# SpeedACQ.net
KiCad netlist of a schematic drawn in Altium Designer
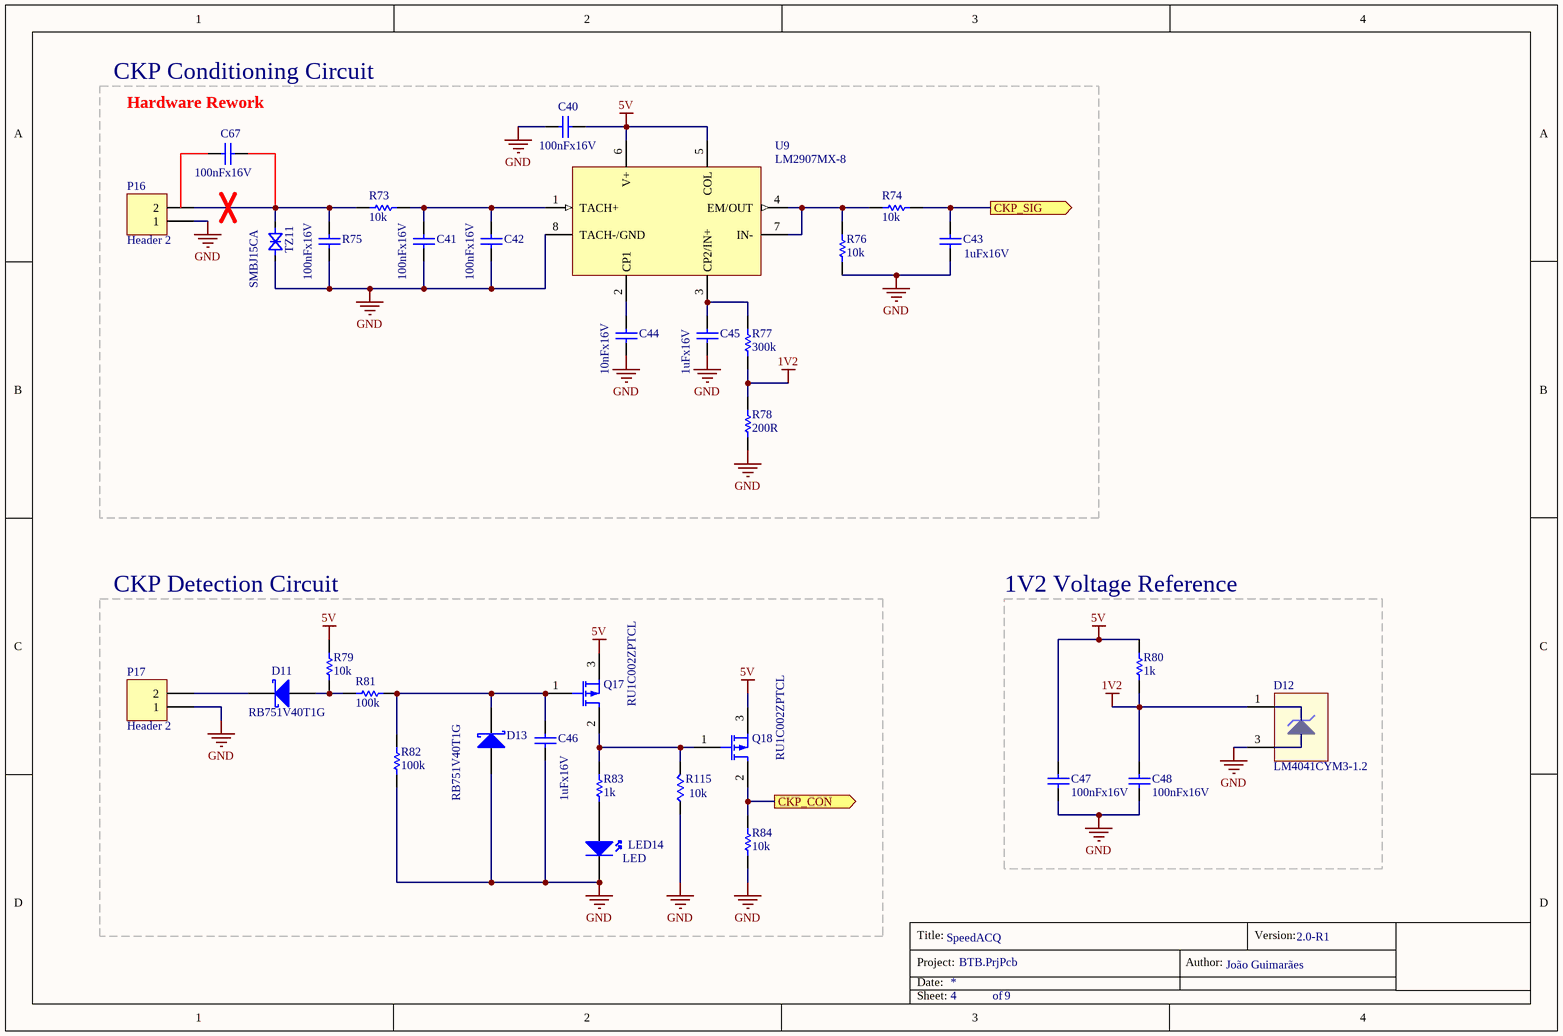
[diagram p0: SpeedACQ.SchDoc]

(export (version "E")
  (design (tool "Eeschema 10.0.6"))
  (components
    (comp (ref "C40")
      (value "100nFx16V")
      (footprint "DISC-0805")
      (description "Capacitor")
      (libsource (lib "IntLib") (part "Cap"))
    )
    (comp (ref "C41")
      (value "100nFx16V")
      (footprint "DISC-0805")
      (description "Capacitor")
      (libsource (lib "IntLib") (part "Cap"))
    )
    (comp (ref "C42")
      (value "100nFx16V")
      (footprint "DISC-0805")
      (description "Capacitor")
      (libsource (lib "IntLib") (part "Cap"))
    )
    (comp (ref "C43")
      (value "1uFx16V")
      (footprint "DISC-0805")
      (description "Capacitor")
      (libsource (lib "IntLib") (part "Cap"))
    )
    (comp (ref "C44")
      (value "10nFx16V")
      (footprint "DISC-0805")
      (description "Capacitor")
      (libsource (lib "IntLib") (part "Cap"))
    )
    (comp (ref "C45")
      (value "1uFx16V")
      (footprint "DISC-0805")
      (description "Capacitor")
      (libsource (lib "IntLib") (part "Cap"))
    )
    (comp (ref "C46")
      (value "1uFx16V")
      (footprint "DISC-0805")
      (description "Capacitor")
      (libsource (lib "IntLib") (part "Cap"))
    )
    (comp (ref "C47")
      (value "100nFx16V")
      (footprint "DISC-0805")
      (description "Capacitor")
      (libsource (lib "IntLib") (part "Cap"))
    )
    (comp (ref "C48")
      (value "100nFx16V")
      (footprint "DISC-0805")
      (description "Capacitor")
      (libsource (lib "IntLib") (part "Cap"))
    )
    (comp (ref "C67")
      (value "100nFx16V")
      (footprint "DISC-0805")
      (description "Capacitor")
      (libsource (lib "IntLib") (part "Cap"))
    )
    (comp (ref "D11")
      (value "RB751V40T1G")
      (footprint "DISC-SOD-323")
      (description "Schottky Diode")
      (fields (field (name "PUBLISHER") "Altium Limited"))
      (libsource (lib "IntLib") (part "D Schottky"))
    )
    (comp (ref "D12")
      (value "LM4041CYM3-1.2")
      (footprint "DISC-SOT-23")
      (description "Shunt Voltage References")
      (libsource (lib "IntLib") (part "LM4040"))
    )
    (comp (ref "D13")
      (value "RB751V40T1G")
      (footprint "DISC-SOD-323")
      (description "Schottky Diode")
      (fields (field (name "PUBLISHER") "Altium Limited"))
      (libsource (lib "IntLib") (part "D Schottky"))
    )
    (comp (ref "LED14") (value "LED") (footprint "DISC-LED-0.1-PTH") (libsource (lib "IntLib") (part "LED")))
    (comp (ref "P16")
      (value "Header 2")
      (footprint "CON-FLEXWIRE-0.5MM2-1X2")
      (description "Header, 2-Pin")
      (fields (field (name "PUBLISHER") "Altium Limited"))
      (libsource (lib "IntLib") (part "Header 2"))
    )
    (comp (ref "P17")
      (value "Header 2")
      (footprint "CON-FLEXWIRE-0.5MM2-1X2")
      (description "Header, 2-Pin")
      (fields (field (name "PUBLISHER") "Altium Limited"))
      (libsource (lib "IntLib") (part "Header 2"))
    )
    (comp (ref "Q17")
      (value "RU1C002ZPTCL")
      (footprint "DISC-SOT-23")
      (description "P-Channel MOSFET")
      (libsource (lib "IntLib") (part "Transistor-PMOS"))
    )
    (comp (ref "Q18")
      (value "RU1C002ZPTCL")
      (footprint "DISC-SOT-23")
      (description "P-Channel MOSFET")
      (libsource (lib "IntLib") (part "Transistor-PMOS"))
    )
    (comp (ref "R73")
      (value "10k")
      (footprint "DISC-0805")
      (description "Resistor")
      (libsource (lib "IntLib") (part "Res"))
    )
    (comp (ref "R74")
      (value "10k")
      (footprint "DISC-0805")
      (description "Resistor")
      (libsource (lib "IntLib") (part "Res"))
    )
    (comp (ref "R75")
      (value "100nFx16V")
      (footprint "DISC-0805")
      (description "Capacitor")
      (libsource (lib "IntLib") (part "Cap"))
    )
    (comp (ref "R76")
      (value "10k")
      (footprint "DISC-0805")
      (description "Resistor")
      (libsource (lib "IntLib") (part "Res"))
    )
    (comp (ref "R77")
      (value "300k")
      (footprint "DISC-0805")
      (description "Resistor")
      (libsource (lib "IntLib") (part "Res"))
    )
    (comp (ref "R78")
      (value "200R")
      (footprint "DISC-0805")
      (description "Resistor")
      (libsource (lib "IntLib") (part "Res"))
    )
    (comp (ref "R79")
      (value "10k")
      (footprint "DISC-0805")
      (description "Resistor")
      (libsource (lib "IntLib") (part "Res"))
    )
    (comp (ref "R80")
      (value "1k")
      (footprint "DISC-0805")
      (description "Resistor")
      (libsource (lib "IntLib") (part "Res"))
    )
    (comp (ref "R81")
      (value "100k")
      (footprint "DISC-0805")
      (description "Resistor")
      (libsource (lib "IntLib") (part "Res"))
    )
    (comp (ref "R82")
      (value "100k")
      (footprint "DISC-0805")
      (description "Resistor")
      (libsource (lib "IntLib") (part "Res"))
    )
    (comp (ref "R83")
      (value "1k")
      (footprint "DISC-0805")
      (description "Resistor")
      (libsource (lib "IntLib") (part "Res"))
    )
    (comp (ref "R84")
      (value "10k")
      (footprint "DISC-0805")
      (description "Resistor")
      (libsource (lib "IntLib") (part "Res"))
    )
    (comp (ref "R115")
      (value "10k")
      (footprint "DISC-0805")
      (description "Resistor")
      (libsource (lib "AUTOTRAC") (part "RESISTOR"))
    )
    (comp (ref "TZ11")
      (value "SMBJ15CA")
      (footprint "DISC-DO214-AA")
      (description "TVZ-Bi-Directional")
      (libsource (lib "IntLib") (part "TVZ-Bi-Directional"))
    )
    (comp (ref "U9")
      (value "LM2907MX-8")
      (footprint "CI-SOIC-8")
      (description "Voltage to Frequency & Frequency to Voltage Frequency to Voltage Converter")
      (libsource (lib "IntLib") (part "LM2907MX-8"))
    )
  )
  (nets
    (net (code "1") (name "/CKP_CON") (class "Default")
      (node (ref "Q18") (pin "2") (pinfunction "D_2") (pintype "passive"))
      (node (ref "R84") (pin "1") (pinfunction "1_1") (pintype "passive"))
    )
    (net (code "2") (name "/CKP_SIG") (class "Default")
      (node (ref "C43") (pin "2") (pinfunction "2_2") (pintype "passive"))
      (node (ref "R74") (pin "2") (pinfunction "2_2") (pintype "passive"))
    )
    (net (code "3") (name "1V2") (class "Default")
      (node (ref "C48") (pin "1") (pinfunction "1_1") (pintype "passive"))
      (node (ref "D12") (pin "1") (pinfunction "A_1") (pintype "passive"))
      (node (ref "R77") (pin "2") (pinfunction "2_2") (pintype "passive"))
      (node (ref "R78") (pin "1") (pinfunction "1_1") (pintype "passive"))
      (node (ref "R80") (pin "2") (pinfunction "2_2") (pintype "passive"))
    )
    (net (code "4") (name "5V") (class "Default")
      (node (ref "C40") (pin "1") (pinfunction "1_1") (pintype "passive"))
      (node (ref "C47") (pin "1") (pinfunction "1_1") (pintype "passive"))
      (node (ref "Q17") (pin "3") (pinfunction "S_3") (pintype "passive"))
      (node (ref "Q18") (pin "3") (pinfunction "S_3") (pintype "passive"))
      (node (ref "R79") (pin "1") (pinfunction "1_1") (pintype "passive"))
      (node (ref "R80") (pin "1") (pinfunction "1_1") (pintype "passive"))
      (node (ref "U9") (pin "5") (pinfunction "COL_5") (pintype "passive"))
      (node (ref "U9") (pin "6") (pinfunction "V+_6") (pintype "power_in"))
    )
    (net (code "5") (name "GND") (class "Default")
      (node (ref "C40") (pin "2") (pinfunction "2_2") (pintype "passive"))
      (node (ref "C41") (pin "1") (pinfunction "1_1") (pintype "passive"))
      (node (ref "C42") (pin "1") (pinfunction "1_1") (pintype "passive"))
      (node (ref "C43") (pin "1") (pinfunction "1_1") (pintype "passive"))
      (node (ref "C44") (pin "1") (pinfunction "1_1") (pintype "passive"))
      (node (ref "C45") (pin "1") (pinfunction "1_1") (pintype "passive"))
      (node (ref "C46") (pin "1") (pinfunction "1_1") (pintype "passive"))
      (node (ref "C47") (pin "2") (pinfunction "2_2") (pintype "passive"))
      (node (ref "C48") (pin "2") (pinfunction "2_2") (pintype "passive"))
      (node (ref "D12") (pin "3") (pinfunction "K_3") (pintype "passive"))
      (node (ref "D13") (pin "1") (pinfunction "A_1") (pintype "passive"))
      (node (ref "LED14") (pin "2") (pinfunction "K_2") (pintype "passive"))
      (node (ref "P16") (pin "1") (pinfunction "1_1") (pintype "passive"))
      (node (ref "P17") (pin "1") (pinfunction "1_1") (pintype "passive"))
      (node (ref "R115") (pin "1") (pintype "passive"))
      (node (ref "R75") (pin "1") (pinfunction "1_1") (pintype "passive"))
      (node (ref "R76") (pin "2") (pinfunction "2_2") (pintype "passive"))
      (node (ref "R78") (pin "2") (pinfunction "2_2") (pintype "passive"))
      (node (ref "R82") (pin "1") (pinfunction "1_1") (pintype "passive"))
      (node (ref "R84") (pin "2") (pinfunction "2_2") (pintype "passive"))
      (node (ref "TZ11") (pin "1") (pinfunction "A_1") (pintype "passive"))
      (node (ref "U9") (pin "8") (pinfunction "TACH-/GND_8") (pintype "power_in"))
    )
    (net (code "6") (name "Net-(D11-A)") (class "Default")
      (node (ref "D11") (pin "1") (pinfunction "A_1") (pintype "passive"))
      (node (ref "R79") (pin "2") (pinfunction "2_2") (pintype "passive"))
      (node (ref "R81") (pin "2") (pinfunction "2_2") (pintype "passive"))
    )
    (net (code "7") (name "Net-(D11-K)") (class "Default")
      (node (ref "D11") (pin "2") (pinfunction "K_2") (pintype "passive"))
      (node (ref "P17") (pin "2") (pinfunction "2_2") (pintype "passive"))
    )
    (net (code "8") (name "Net-(D13-K)") (class "Default")
      (node (ref "C46") (pin "2") (pinfunction "2_2") (pintype "passive"))
      (node (ref "D13") (pin "2") (pinfunction "K_2") (pintype "passive"))
      (node (ref "Q17") (pin "1") (pinfunction "G_1") (pintype "passive"))
      (node (ref "R81") (pin "1") (pinfunction "1_1") (pintype "passive"))
      (node (ref "R82") (pin "2") (pinfunction "2_2") (pintype "passive"))
    )
    (net (code "9") (name "Net-(LED14-A)") (class "Default")
      (node (ref "LED14") (pin "1") (pinfunction "A_1") (pintype "passive"))
      (node (ref "R83") (pin "1") (pinfunction "1_1") (pintype "passive"))
    )
    (net (code "10") (name "Net-(Q17-D)") (class "Default")
      (node (ref "Q17") (pin "2") (pinfunction "D_2") (pintype "passive"))
      (node (ref "Q18") (pin "1") (pinfunction "G_1") (pintype "passive"))
      (node (ref "R115") (pin "2") (pintype "passive"))
      (node (ref "R83") (pin "2") (pinfunction "2_2") (pintype "passive"))
    )
    (net (code "11") (name "Net-(TZ11-K)") (class "Default")
      (node (ref "C67") (pin "2") (pinfunction "2_2") (pintype "passive"))
      (node (ref "P16") (pin "2") (pinfunction "2_2") (pintype "passive"))
      (node (ref "R73") (pin "2") (pinfunction "2_2") (pintype "passive"))
      (node (ref "R75") (pin "2") (pinfunction "2_2") (pintype "passive"))
      (node (ref "TZ11") (pin "2") (pinfunction "K_2") (pintype "passive"))
    )
    (net (code "12") (name "Net-(U9-CP1)") (class "Default")
      (node (ref "C44") (pin "2") (pinfunction "2_2") (pintype "passive"))
      (node (ref "U9") (pin "2") (pinfunction "CP1_2") (pintype "passive"))
    )
    (net (code "13") (name "Net-(U9-CP2{slash}IN+)") (class "Default")
      (node (ref "C45") (pin "2") (pinfunction "2_2") (pintype "passive"))
      (node (ref "R77") (pin "1") (pinfunction "1_1") (pintype "passive"))
      (node (ref "U9") (pin "3") (pinfunction "CP2/IN+_3") (pintype "passive"))
    )
    (net (code "14") (name "Net-(U9-EM{slash}OUT)") (class "Default")
      (node (ref "R74") (pin "1") (pinfunction "1_1") (pintype "passive"))
      (node (ref "R76") (pin "1") (pinfunction "1_1") (pintype "passive"))
      (node (ref "U9") (pin "4") (pinfunction "EM/OUT_4") (pintype "output"))
      (node (ref "U9") (pin "7") (pinfunction "IN-_7") (pintype "passive"))
    )
    (net (code "15") (name "Net-(U9-TACH+)") (class "Default")
      (node (ref "C41") (pin "2") (pinfunction "2_2") (pintype "passive"))
      (node (ref "C42") (pin "2") (pinfunction "2_2") (pintype "passive"))
      (node (ref "R73") (pin "1") (pinfunction "1_1") (pintype "passive"))
      (node (ref "U9") (pin "1") (pinfunction "TACH+_1") (pintype "input"))
    )
    (net (code "16") (name "unconnected-(C67-Pad1)") (class "Default")
      (node (ref "C67") (pin "1") (pinfunction "1_1") (pintype "passive"))
    )
    (net (code "17") (name "unconnected-(D12-Pad2)") (class "Default")
      (node (ref "D12") (pin "2") (pinfunction "2_2") (pintype "passive"))
    )
  )
)
